# 4_ADC_Filter.net
KiCad netlist of a schematic drawn in Altium Designer
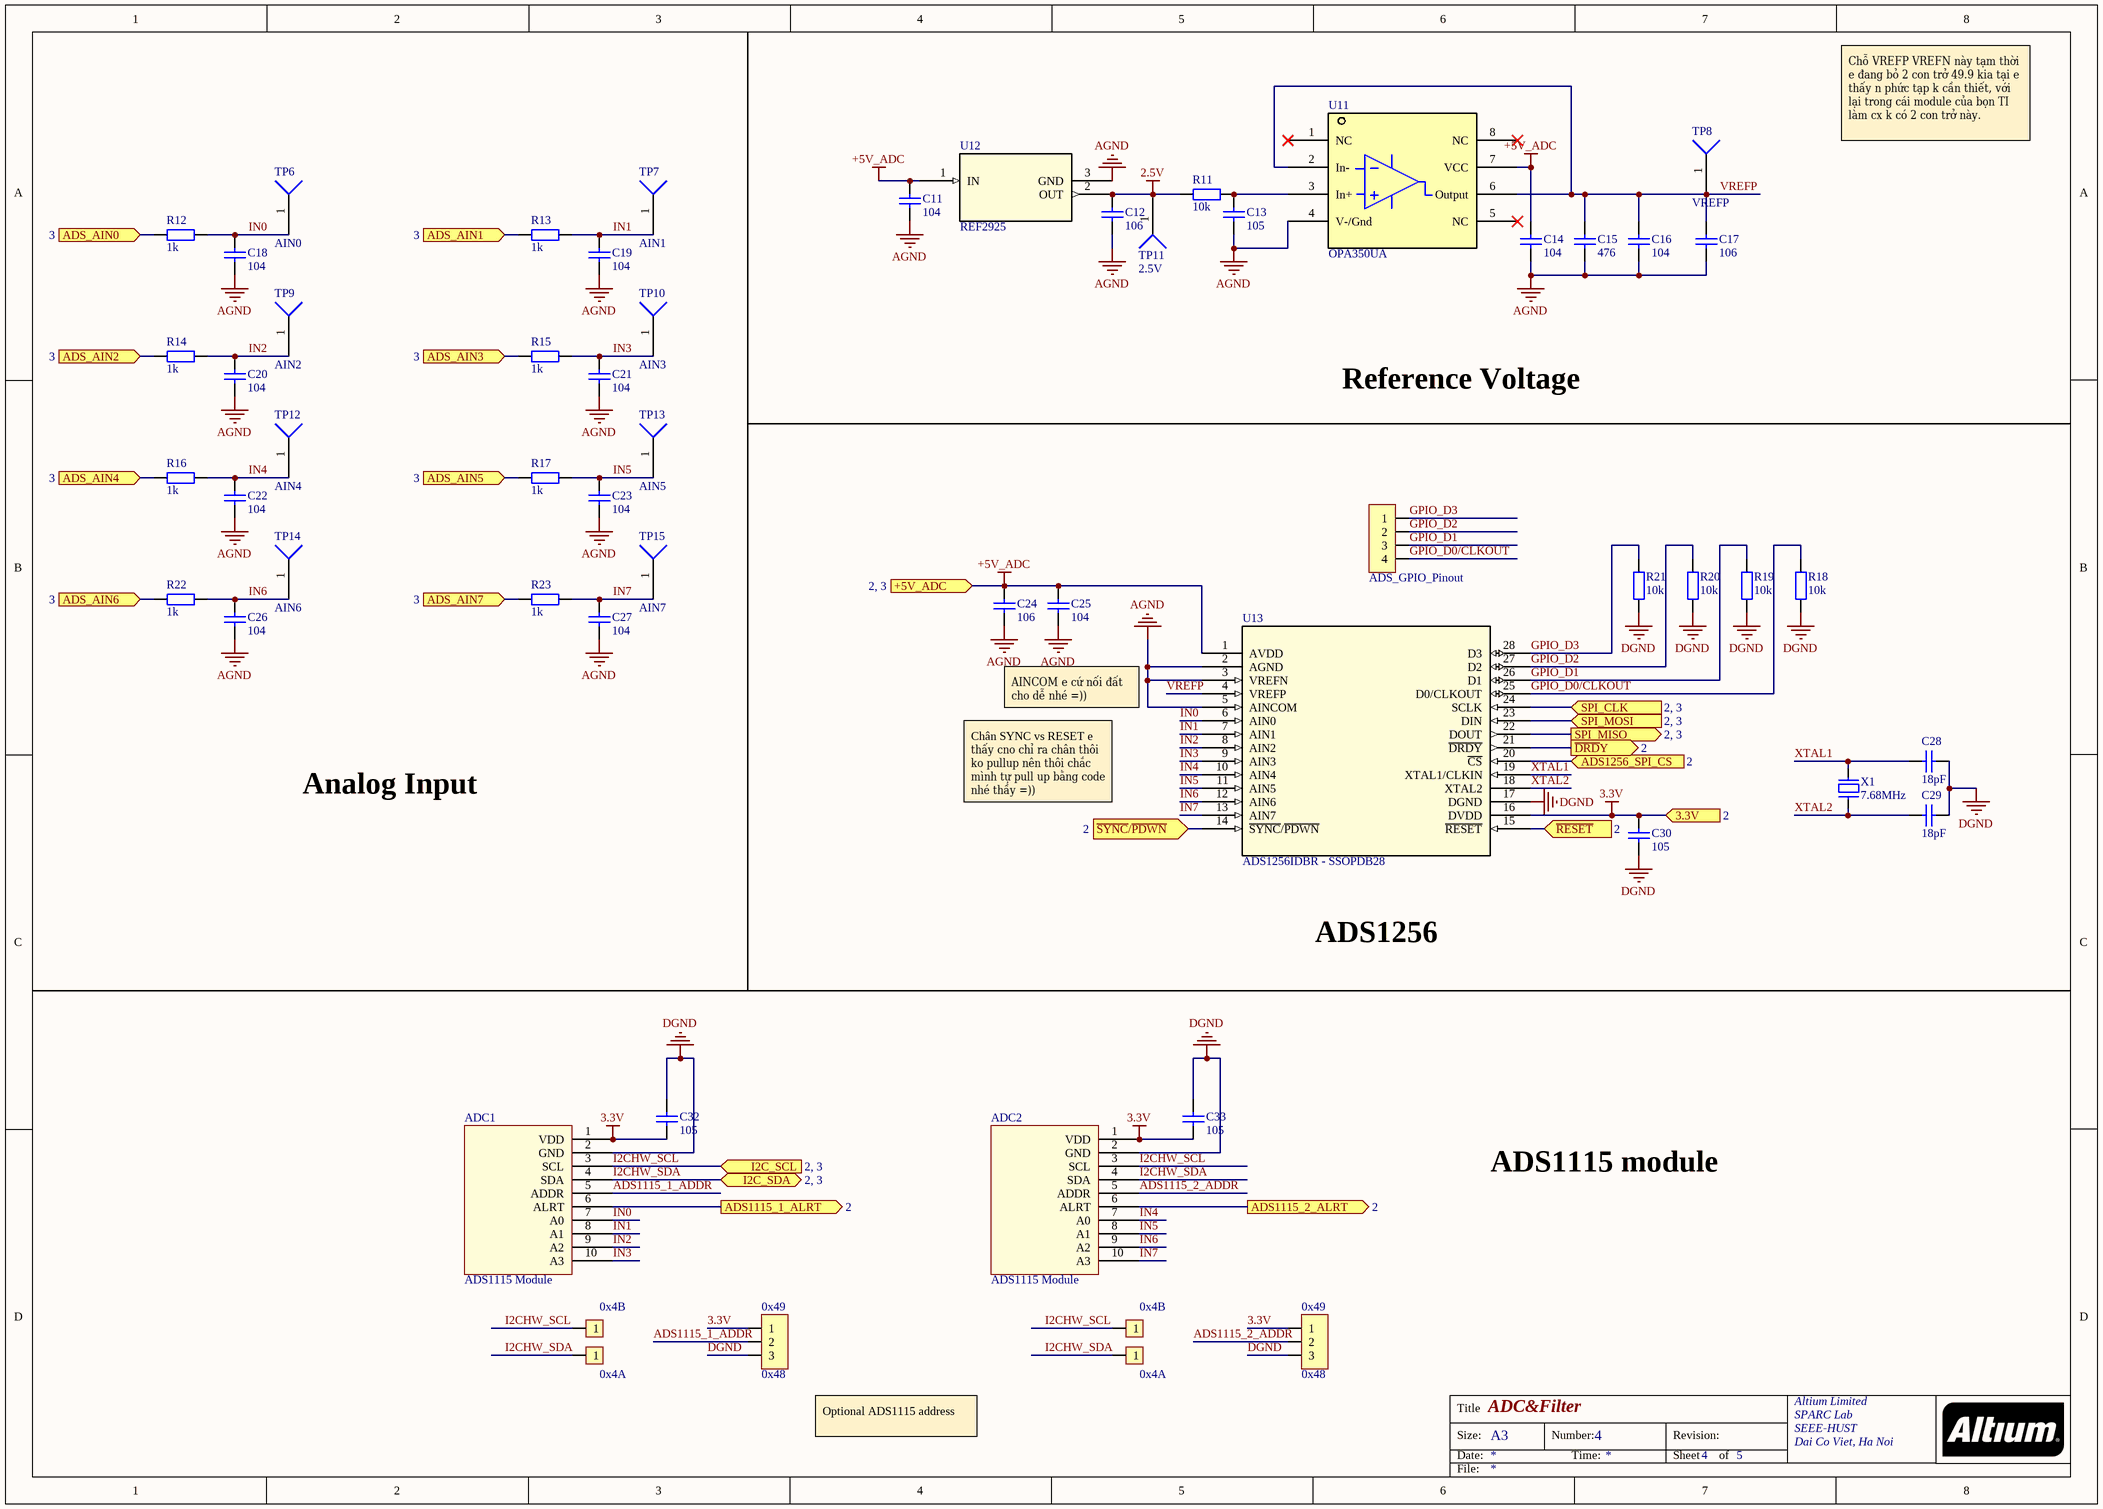
[diagram p0: [4]ADC&Filter.SchDoc]

(export (version "E")
  (design (tool "Eeschema 10.0.6"))
  (components
    (comp (ref "ADC1")
      (value "ADS1115 Module")
      (footprint "ADS1115")
      (libsource (lib "Module1") (part "ADS1115 Module ADC"))
    )
    (comp (ref "ADC2")
      (value "ADS1115 Module")
      (footprint "ADS1115")
      (libsource (lib "Module1") (part "ADS1115 Module ADC"))
    )
    (comp (ref "C11")
      (value "104")
      (footprint "tu 0805")
      (description "Dán")
      (libsource (lib "Tu dien") (part "Tu 0805 104 50V 10%"))
    )
    (comp (ref "C12")
      (value "106")
      (footprint "tu 0805")
      (description "Dán")
      (libsource (lib "Tu dien") (part "Tu 0805 106 16V 10%"))
    )
    (comp (ref "C13")
      (value "105")
      (footprint "tu 0805")
      (description "Dán")
      (libsource (lib "Tu dien") (part "Tu 0805 105 50V 10%"))
    )
    (comp (ref "C14")
      (value "104")
      (footprint "tu 0805")
      (description "Dán")
      (libsource (lib "Tu dien") (part "Tu 0805 104 50V 10%"))
    )
    (comp (ref "C15")
      (value "476")
      (footprint "tu 0805")
      (description "Dán")
      (libsource (lib "Tu dien") (part "Tu 0805 475 25V 20%"))
    )
    (comp (ref "C16")
      (value "104")
      (footprint "tu 0805")
      (description "Dán")
      (libsource (lib "Tu dien") (part "Tu 0805 104 50V 10%"))
    )
    (comp (ref "C17")
      (value "106")
      (footprint "tu 0805")
      (description "Dán")
      (libsource (lib "Tu dien") (part "Tu 0805 106 16V 10%"))
    )
    (comp (ref "C18")
      (value "104")
      (footprint "tu 0805")
      (description "Dán")
      (libsource (lib "Tu dien") (part "Tu 0805 104 50V 10%"))
    )
    (comp (ref "C19")
      (value "104")
      (footprint "tu 0805")
      (description "Dán")
      (libsource (lib "Tu dien") (part "Tu 0805 104 50V 10%"))
    )
    (comp (ref "C20")
      (value "104")
      (footprint "tu 0805")
      (description "Dán")
      (libsource (lib "Tu dien") (part "Tu 0805 104 50V 10%"))
    )
    (comp (ref "C21")
      (value "104")
      (footprint "tu 0805")
      (description "Dán")
      (libsource (lib "Tu dien") (part "Tu 0805 104 50V 10%"))
    )
    (comp (ref "C22")
      (value "104")
      (footprint "tu 0805")
      (description "Dán")
      (libsource (lib "Tu dien") (part "Tu 0805 104 50V 10%"))
    )
    (comp (ref "C23")
      (value "104")
      (footprint "tu 0805")
      (description "Dán")
      (libsource (lib "Tu dien") (part "Tu 0805 104 50V 10%"))
    )
    (comp (ref "C24")
      (value "106")
      (footprint "tu 0805")
      (description "Dán")
      (libsource (lib "Tu dien") (part "Tu 0805 106 16V 10%"))
    )
    (comp (ref "C25")
      (value "104")
      (footprint "tu 0805")
      (description "Dán")
      (libsource (lib "Tu dien") (part "Tu 0805 104 50V 10%"))
    )
    (comp (ref "C26")
      (value "104")
      (footprint "tu 0805")
      (description "Dán")
      (libsource (lib "Tu dien") (part "Tu 0805 104 50V 10%"))
    )
    (comp (ref "C27")
      (value "104")
      (footprint "tu 0805")
      (description "Dán")
      (libsource (lib "Tu dien") (part "Tu 0805 104 50V 10%"))
    )
    (comp (ref "C28")
      (value "18pF")
      (footprint "tu 0805")
      (description "Dán")
      (libsource (lib "Tu dien") (part "Tu 0805 18pF 50V 10%_1"))
    )
    (comp (ref "C29")
      (value "18pF")
      (footprint "tu 0805")
      (description "Dán")
      (libsource (lib "Tu dien") (part "Tu 0805 18pF 50V 10%_1"))
    )
    (comp (ref "C30")
      (value "105")
      (footprint "tu 0805")
      (description "Dán")
      (libsource (lib "Tu dien") (part "Tu 0805 105 50V 10%"))
    )
    (comp (ref "C32")
      (value "105")
      (footprint "tu 0805")
      (description "Dán")
      (libsource (lib "Tu dien") (part "Tu 0805 105 50V 10%"))
    )
    (comp (ref "C33")
      (value "105")
      (footprint "tu 0805")
      (description "Dán")
      (libsource (lib "Tu dien") (part "Tu 0805 105 50V 10%"))
    )
    (comp (ref "JP1")
      (value "ADS_GPIO_Pinout")
      (footprint "JP 1x4 DT")
      (description "Cắm")
      (libsource (lib "Jump") (part "JP 1x4 2.54 Duc Thang"))
    )
    (comp (ref "JP5")
      (value "JP 1x3 2.54")
      (footprint "JP 1x3 DT")
      (description "Cắm")
      (libsource (lib "Jump") (part "JP 1x3 2.54 Duc Thang"))
    )
    (comp (ref "JP6")
      (value "JP 1x3 2.54")
      (footprint "JP 1x3 DT")
      (description "Cắm")
      (libsource (lib "Jump") (part "JP 1x3 2.54 Duc Thang"))
    )
    (comp (ref "JP7")
      (value "JP 1x1 2.54")
      (footprint "JP 1x1 DT")
      (description "Cắm")
      (libsource (lib "Jump") (part "JP 1x1 2.54 Duc Thang"))
    )
    (comp (ref "JP8")
      (value "JP 1x1 2.54")
      (footprint "JP 1x1 DT")
      (description "Cắm")
      (libsource (lib "Jump") (part "JP 1x1 2.54 Duc Thang"))
    )
    (comp (ref "JP9")
      (value "JP 1x1 2.54")
      (footprint "JP 1x1 DT")
      (description "Cắm")
      (libsource (lib "Jump") (part "JP 1x1 2.54 Duc Thang"))
    )
    (comp (ref "JP10")
      (value "JP 1x1 2.54")
      (footprint "JP 1x1 DT")
      (description "Cắm")
      (libsource (lib "Jump") (part "JP 1x1 2.54 Duc Thang"))
    )
    (comp (ref "R11")
      (value "10k")
      (footprint "tro smd 0805")
      (description "Dán")
      (libsource (lib "Dien Tro") (part "Tro 0805 1% 10k"))
    )
    (comp (ref "R12")
      (value "1k")
      (footprint "tro smd 0805")
      (description "Dán")
      (libsource (lib "Dien Tro") (part "Tro 0805 1% 1k"))
    )
    (comp (ref "R13")
      (value "1k")
      (footprint "tro smd 0805")
      (description "Dán")
      (libsource (lib "Dien Tro") (part "Tro 0805 1% 1k"))
    )
    (comp (ref "R14")
      (value "1k")
      (footprint "tro smd 0805")
      (description "Dán")
      (libsource (lib "Dien Tro") (part "Tro 0805 1% 1k"))
    )
    (comp (ref "R15")
      (value "1k")
      (footprint "tro smd 0805")
      (description "Dán")
      (libsource (lib "Dien Tro") (part "Tro 0805 1% 1k"))
    )
    (comp (ref "R16")
      (value "1k")
      (footprint "tro smd 0805")
      (description "Dán")
      (libsource (lib "Dien Tro") (part "Tro 0805 1% 1k"))
    )
    (comp (ref "R17")
      (value "1k")
      (footprint "tro smd 0805")
      (description "Dán")
      (libsource (lib "Dien Tro") (part "Tro 0805 1% 1k"))
    )
    (comp (ref "R18")
      (value "10k")
      (footprint "tro smd 0805")
      (description "Dán")
      (libsource (lib "Dien Tro") (part "Tro 0805 1% 10k"))
    )
    (comp (ref "R19")
      (value "10k")
      (footprint "tro smd 0805")
      (description "Dán")
      (libsource (lib "Dien Tro") (part "Tro 0805 1% 10k"))
    )
    (comp (ref "R20")
      (value "10k")
      (footprint "tro smd 0805")
      (description "Dán")
      (libsource (lib "Dien Tro") (part "Tro 0805 1% 10k"))
    )
    (comp (ref "R21")
      (value "10k")
      (footprint "tro smd 0805")
      (description "Dán")
      (libsource (lib "Dien Tro") (part "Tro 0805 1% 10k"))
    )
    (comp (ref "R22")
      (value "1k")
      (footprint "tro smd 0805")
      (description "Dán")
      (libsource (lib "Dien Tro") (part "Tro 0805 1% 1k"))
    )
    (comp (ref "R23")
      (value "1k")
      (footprint "tro smd 0805")
      (description "Dán")
      (libsource (lib "Dien Tro") (part "Tro 0805 1% 1k"))
    )
    (comp (ref "TP6")
      (value "AIN0")
      (footprint "MinhTien_PCBLib:pad_1.65x1.65_hole_1mm")
      (description "Test Point")
      (fields (field (name "PUBLISHER") "Altium Limited"))
      (libsource (lib "MinhTien_SCHLib") (part "Test Point"))
    )
    (comp (ref "TP7")
      (value "AIN1")
      (footprint "MinhTien_PCBLib:pad_1.65x1.65_hole_1mm")
      (description "Test Point")
      (fields (field (name "PUBLISHER") "Altium Limited"))
      (libsource (lib "MinhTien_SCHLib") (part "Test Point"))
    )
    (comp (ref "TP8")
      (value "VREFP")
      (footprint "MinhTien_PCBLib:pad_1.65x1.65_hole_1mm")
      (description "Test Point")
      (fields (field (name "PUBLISHER") "Altium Limited"))
      (libsource (lib "MinhTien_SCHLib") (part "Test Point"))
    )
    (comp (ref "TP9")
      (value "AIN2")
      (footprint "MinhTien_PCBLib:pad_1.65x1.65_hole_1mm")
      (description "Test Point")
      (fields (field (name "PUBLISHER") "Altium Limited"))
      (libsource (lib "MinhTien_SCHLib") (part "Test Point"))
    )
    (comp (ref "TP10")
      (value "AIN3")
      (footprint "MinhTien_PCBLib:pad_1.65x1.65_hole_1mm")
      (description "Test Point")
      (fields (field (name "PUBLISHER") "Altium Limited"))
      (libsource (lib "MinhTien_SCHLib") (part "Test Point"))
    )
    (comp (ref "TP11")
      (value "2.5V")
      (footprint "MinhTien_PCBLib:pad_1.65x1.65_hole_1mm")
      (description "Test Point")
      (fields (field (name "PUBLISHER") "Altium Limited"))
      (libsource (lib "MinhTien_SCHLib") (part "Test Point"))
    )
    (comp (ref "TP12")
      (value "AIN4")
      (footprint "MinhTien_PCBLib:pad_1.65x1.65_hole_1mm")
      (description "Test Point")
      (fields (field (name "PUBLISHER") "Altium Limited"))
      (libsource (lib "MinhTien_SCHLib") (part "Test Point"))
    )
    (comp (ref "TP13")
      (value "AIN5")
      (footprint "MinhTien_PCBLib:pad_1.65x1.65_hole_1mm")
      (description "Test Point")
      (fields (field (name "PUBLISHER") "Altium Limited"))
      (libsource (lib "MinhTien_SCHLib") (part "Test Point"))
    )
    (comp (ref "TP14")
      (value "AIN6")
      (footprint "MinhTien_PCBLib:pad_1.65x1.65_hole_1mm")
      (description "Test Point")
      (fields (field (name "PUBLISHER") "Altium Limited"))
      (libsource (lib "MinhTien_SCHLib") (part "Test Point"))
    )
    (comp (ref "TP15")
      (value "AIN7")
      (footprint "MinhTien_PCBLib:pad_1.65x1.65_hole_1mm")
      (description "Test Point")
      (fields (field (name "PUBLISHER") "Altium Limited"))
      (libsource (lib "MinhTien_SCHLib") (part "Test Point"))
    )
    (comp (ref "U11")
      (value "OPA350UA")
      (footprint "IC:SOIC 8_127P599X175")
      (description "Op-amp OPA350")
      (libsource (lib "IC") (part "OPA350"))
    )
    (comp (ref "U12")
      (value "REF2925")
      (footprint "IC:SOT23-DBZ3")
      (description "SOT-23 CMOS 2.5V Voltage Reference")
      (libsource (lib "IC") (part "REF2925AIDBZR"))
    )
    (comp (ref "U13")
      (value "ADS1256IDBR - SSOPDB28")
      (footprint "IC:SSOPDB28")
      (description "Very Low Noise, 24-Bit Analog-to-Digital Converter")
      (libsource (lib "IC") (part "ADS1256IDBR - SSOPDB28"))
    )
    (comp (ref "X1")
      (value "7.68MHz")
      (footprint "Thach Anh 2 chan SMD")
      (description "Crystal For all Crystal 2pin.")
      (libsource (lib "Component") (part "Thach Anh 2 chan SMD"))
    )
  )
  (nets
    (net (code "1") (name "+5V_ADC") (class "Default")
      (node (ref "C11") (pin "1") (pinfunction "1_1") (pintype "passive"))
      (node (ref "C14") (pin "1") (pinfunction "1_1") (pintype "passive"))
      (node (ref "C24") (pin "1") (pinfunction "1_1") (pintype "passive"))
      (node (ref "C25") (pin "1") (pinfunction "1_1") (pintype "passive"))
      (node (ref "U11") (pin "7") (pinfunction "VCC_7") (pintype "passive"))
      (node (ref "U12") (pin "1") (pinfunction "IN_1") (pintype "input"))
      (node (ref "U13") (pin "1") (pinfunction "AVDD_1") (pintype "power_in"))
    )
    (net (code "2") (name "/ADS1115_1_ADDR") (class "Default")
      (node (ref "ADC1") (pin "5") (pinfunction "ADDR_5") (pintype "passive"))
      (node (ref "JP5") (pin "2") (pinfunction "2_2") (pintype "passive"))
    )
    (net (code "3") (name "/ADS1115_1_ALRT") (class "Default")
      (node (ref "ADC1") (pin "6") (pinfunction "ALRT_6") (pintype "passive"))
    )
    (net (code "4") (name "/ADS1115_2_ADDR") (class "Default")
      (node (ref "ADC2") (pin "5") (pinfunction "ADDR_5") (pintype "passive"))
      (node (ref "JP6") (pin "2") (pinfunction "2_2") (pintype "passive"))
    )
    (net (code "5") (name "/ADS1115_2_ALRT") (class "Default")
      (node (ref "ADC2") (pin "6") (pinfunction "ALRT_6") (pintype "passive"))
    )
    (net (code "6") (name "/ADS1256_SPI_CS") (class "Default")
      (node (ref "U13") (pin "20") (pinfunction "~{CS}_20") (pintype "input"))
    )
    (net (code "7") (name "/ADS_AIN0") (class "Default")
      (node (ref "R12") (pin "1") (pinfunction "1_1") (pintype "passive"))
    )
    (net (code "8") (name "/ADS_AIN1") (class "Default")
      (node (ref "R13") (pin "1") (pinfunction "1_1") (pintype "passive"))
    )
    (net (code "9") (name "/ADS_AIN2") (class "Default")
      (node (ref "R14") (pin "1") (pinfunction "1_1") (pintype "passive"))
    )
    (net (code "10") (name "/ADS_AIN3") (class "Default")
      (node (ref "R15") (pin "1") (pinfunction "1_1") (pintype "passive"))
    )
    (net (code "11") (name "/ADS_AIN4") (class "Default")
      (node (ref "R16") (pin "1") (pinfunction "1_1") (pintype "passive"))
    )
    (net (code "12") (name "/ADS_AIN5") (class "Default")
      (node (ref "R17") (pin "1") (pinfunction "1_1") (pintype "passive"))
    )
    (net (code "13") (name "/ADS_AIN6") (class "Default")
      (node (ref "R22") (pin "1") (pinfunction "1_1") (pintype "passive"))
    )
    (net (code "14") (name "/ADS_AIN7") (class "Default")
      (node (ref "R23") (pin "1") (pinfunction "1_1") (pintype "passive"))
    )
    (net (code "15") (name "/GPIO_D0{slash}CLKOUT") (class "Default")
      (node (ref "JP1") (pin "4") (pinfunction "4_4") (pintype "passive"))
      (node (ref "R18") (pin "2") (pinfunction "2_2") (pintype "passive"))
      (node (ref "U13") (pin "25") (pinfunction "D0/CLKOUT_25") (pintype "bidirectional"))
    )
    (net (code "16") (name "/GPIO_D1") (class "Default")
      (node (ref "JP1") (pin "3") (pinfunction "3_3") (pintype "passive"))
      (node (ref "R19") (pin "1") (pinfunction "1_1") (pintype "passive"))
      (node (ref "U13") (pin "26") (pinfunction "D1_26") (pintype "bidirectional"))
    )
    (net (code "17") (name "/GPIO_D2") (class "Default")
      (node (ref "JP1") (pin "2") (pinfunction "2_2") (pintype "passive"))
      (node (ref "R20") (pin "1") (pinfunction "1_1") (pintype "passive"))
      (node (ref "U13") (pin "27") (pinfunction "D2_27") (pintype "bidirectional"))
    )
    (net (code "18") (name "/GPIO_D3") (class "Default")
      (node (ref "JP1") (pin "1") (pinfunction "1_1") (pintype "passive"))
      (node (ref "R21") (pin "1") (pinfunction "1_1") (pintype "passive"))
      (node (ref "U13") (pin "28") (pinfunction "D3_28") (pintype "bidirectional"))
    )
    (net (code "19") (name "/I2CHW_SCL") (class "Default")
      (node (ref "ADC1") (pin "3") (pinfunction "SCL_3") (pintype "passive"))
      (node (ref "ADC2") (pin "3") (pinfunction "SCL_3") (pintype "passive"))
      (node (ref "JP7") (pin "1") (pinfunction "1_1") (pintype "passive"))
      (node (ref "JP8") (pin "1") (pinfunction "1_1") (pintype "passive"))
    )
    (net (code "20") (name "/I2CHW_SDA") (class "Default")
      (node (ref "ADC1") (pin "4") (pinfunction "SDA_4") (pintype "passive"))
      (node (ref "ADC2") (pin "4") (pinfunction "SDA_4") (pintype "passive"))
      (node (ref "JP10") (pin "1") (pinfunction "1_1") (pintype "passive"))
      (node (ref "JP9") (pin "1") (pinfunction "1_1") (pintype "passive"))
    )
    (net (code "21") (name "/IN0") (class "Default")
      (node (ref "ADC1") (pin "7") (pinfunction "A0_7") (pintype "passive"))
      (node (ref "C18") (pin "1") (pinfunction "1_1") (pintype "passive"))
      (node (ref "R12") (pin "2") (pinfunction "2_2") (pintype "passive"))
      (node (ref "TP6") (pin "1") (pinfunction "1_1") (pintype "passive"))
      (node (ref "U13") (pin "6") (pinfunction "AIN0_6") (pintype "input"))
    )
    (net (code "22") (name "/IN1") (class "Default")
      (node (ref "ADC1") (pin "8") (pinfunction "A1_8") (pintype "passive"))
      (node (ref "C19") (pin "1") (pinfunction "1_1") (pintype "passive"))
      (node (ref "R13") (pin "2") (pinfunction "2_2") (pintype "passive"))
      (node (ref "TP7") (pin "1") (pinfunction "1_1") (pintype "passive"))
      (node (ref "U13") (pin "7") (pinfunction "AIN1_7") (pintype "input"))
    )
    (net (code "23") (name "/IN2") (class "Default")
      (node (ref "ADC1") (pin "9") (pinfunction "A2_9") (pintype "passive"))
      (node (ref "C20") (pin "1") (pinfunction "1_1") (pintype "passive"))
      (node (ref "R14") (pin "2") (pinfunction "2_2") (pintype "passive"))
      (node (ref "TP9") (pin "1") (pinfunction "1_1") (pintype "passive"))
      (node (ref "U13") (pin "8") (pinfunction "AIN2_8") (pintype "input"))
    )
    (net (code "24") (name "/IN3") (class "Default")
      (node (ref "ADC1") (pin "10") (pinfunction "A3_10") (pintype "passive"))
      (node (ref "C21") (pin "1") (pinfunction "1_1") (pintype "passive"))
      (node (ref "R15") (pin "2") (pinfunction "2_2") (pintype "passive"))
      (node (ref "TP10") (pin "1") (pinfunction "1_1") (pintype "passive"))
      (node (ref "U13") (pin "9") (pinfunction "AIN3_9") (pintype "input"))
    )
    (net (code "25") (name "/IN4") (class "Default")
      (node (ref "ADC2") (pin "7") (pinfunction "A0_7") (pintype "passive"))
      (node (ref "C22") (pin "1") (pinfunction "1_1") (pintype "passive"))
      (node (ref "R16") (pin "2") (pinfunction "2_2") (pintype "passive"))
      (node (ref "TP12") (pin "1") (pinfunction "1_1") (pintype "passive"))
      (node (ref "U13") (pin "10") (pinfunction "AIN4_10") (pintype "input"))
    )
    (net (code "26") (name "/IN5") (class "Default")
      (node (ref "ADC2") (pin "8") (pinfunction "A1_8") (pintype "passive"))
      (node (ref "C23") (pin "1") (pinfunction "1_1") (pintype "passive"))
      (node (ref "R17") (pin "2") (pinfunction "2_2") (pintype "passive"))
      (node (ref "TP13") (pin "1") (pinfunction "1_1") (pintype "passive"))
      (node (ref "U13") (pin "11") (pinfunction "AIN5_11") (pintype "input"))
    )
    (net (code "27") (name "/IN6") (class "Default")
      (node (ref "ADC2") (pin "9") (pinfunction "A2_9") (pintype "passive"))
      (node (ref "C26") (pin "1") (pinfunction "1_1") (pintype "passive"))
      (node (ref "R22") (pin "2") (pinfunction "2_2") (pintype "passive"))
      (node (ref "TP14") (pin "1") (pinfunction "1_1") (pintype "passive"))
      (node (ref "U13") (pin "12") (pinfunction "AIN6_12") (pintype "input"))
    )
    (net (code "28") (name "/IN7") (class "Default")
      (node (ref "ADC2") (pin "10") (pinfunction "A3_10") (pintype "passive"))
      (node (ref "C27") (pin "1") (pinfunction "1_1") (pintype "passive"))
      (node (ref "R23") (pin "2") (pinfunction "2_2") (pintype "passive"))
      (node (ref "TP15") (pin "1") (pinfunction "1_1") (pintype "passive"))
      (node (ref "U13") (pin "13") (pinfunction "AIN7_13") (pintype "input"))
    )
    (net (code "29") (name "/SPI_CLK") (class "Default")
      (node (ref "U13") (pin "24") (pinfunction "SCLK_24") (pintype "input"))
    )
    (net (code "30") (name "/SPI_MISO") (class "Default")
      (node (ref "U13") (pin "22") (pinfunction "DOUT_22") (pintype "output"))
    )
    (net (code "31") (name "/SPI_MOSI") (class "Default")
      (node (ref "U13") (pin "23") (pinfunction "DIN_23") (pintype "input"))
    )
    (net (code "32") (name "/VREFP") (class "Default")
      (node (ref "C15") (pin "1") (pinfunction "1_1") (pintype "passive"))
      (node (ref "C16") (pin "1") (pinfunction "1_1") (pintype "passive"))
      (node (ref "C17") (pin "1") (pinfunction "1_1") (pintype "passive"))
      (node (ref "TP8") (pin "1") (pinfunction "1_1") (pintype "passive"))
      (node (ref "U11") (pin "2") (pinfunction "In-_2") (pintype "passive"))
      (node (ref "U11") (pin "6") (pinfunction "Output_6") (pintype "passive"))
      (node (ref "U13") (pin "4") (pinfunction "VREFP_4") (pintype "input"))
    )
    (net (code "33") (name "/XTAL1") (class "Default")
      (node (ref "C28") (pin "2") (pinfunction "2_2") (pintype "passive"))
      (node (ref "U13") (pin "19") (pinfunction "XTAL1/CLKIN_19") (pintype "input"))
      (node (ref "X1") (pin "2") (pinfunction "2_2") (pintype "passive"))
    )
    (net (code "34") (name "/XTAL2") (class "Default")
      (node (ref "C29") (pin "2") (pinfunction "2_2") (pintype "passive"))
      (node (ref "U13") (pin "18") (pinfunction "XTAL2_18") (pintype "passive"))
      (node (ref "X1") (pin "1") (pinfunction "1_1") (pintype "passive"))
    )
    (net (code "35") (name "/~{DRD}Y") (class "Default")
      (node (ref "U13") (pin "21") (pinfunction "~{DRDY}_21") (pintype "output"))
    )
    (net (code "36") (name "/~{RESET}") (class "Default")
      (node (ref "U13") (pin "15") (pinfunction "~{RESET}_15") (pintype "input"))
    )
    (net (code "37") (name "/~{SYNC}{slash}~{PDWN}") (class "Default")
      (node (ref "U13") (pin "14") (pinfunction "~{SYNC}/~{PDWN}_14") (pintype "input"))
    )
    (net (code "38") (name "2.5V") (class "Default")
      (node (ref "C12") (pin "1") (pinfunction "1_1") (pintype "passive"))
      (node (ref "R11") (pin "1") (pinfunction "1_1") (pintype "passive"))
      (node (ref "TP11") (pin "1") (pinfunction "1_1") (pintype "passive"))
      (node (ref "U12") (pin "2") (pinfunction "OUT_2") (pintype "output"))
    )
    (net (code "39") (name "3.3V") (class "Default")
      (node (ref "ADC1") (pin "1") (pinfunction "VDD_1") (pintype "passive"))
      (node (ref "ADC2") (pin "1") (pinfunction "VDD_1") (pintype "passive"))
      (node (ref "C30") (pin "1") (pinfunction "1_1") (pintype "passive"))
      (node (ref "C32") (pin "1") (pinfunction "1_1") (pintype "passive"))
      (node (ref "C33") (pin "1") (pinfunction "1_1") (pintype "passive"))
      (node (ref "JP5") (pin "1") (pinfunction "1_1") (pintype "passive"))
      (node (ref "JP6") (pin "1") (pinfunction "1_1") (pintype "passive"))
      (node (ref "U13") (pin "16") (pinfunction "DVDD_16") (pintype "power_in"))
    )
    (net (code "40") (name "AGND") (class "Default")
      (node (ref "C11") (pin "2") (pinfunction "2_2") (pintype "passive"))
      (node (ref "C12") (pin "2") (pinfunction "2_2") (pintype "passive"))
      (node (ref "C13") (pin "2") (pinfunction "2_2") (pintype "passive"))
      (node (ref "C14") (pin "2") (pinfunction "2_2") (pintype "passive"))
      (node (ref "C15") (pin "2") (pinfunction "2_2") (pintype "passive"))
      (node (ref "C16") (pin "2") (pinfunction "2_2") (pintype "passive"))
      (node (ref "C17") (pin "2") (pinfunction "2_2") (pintype "passive"))
      (node (ref "C18") (pin "2") (pinfunction "2_2") (pintype "passive"))
      (node (ref "C19") (pin "2") (pinfunction "2_2") (pintype "passive"))
      (node (ref "C20") (pin "2") (pinfunction "2_2") (pintype "passive"))
      (node (ref "C21") (pin "2") (pinfunction "2_2") (pintype "passive"))
      (node (ref "C22") (pin "2") (pinfunction "2_2") (pintype "passive"))
      (node (ref "C23") (pin "2") (pinfunction "2_2") (pintype "passive"))
      (node (ref "C24") (pin "2") (pinfunction "2_2") (pintype "passive"))
      (node (ref "C25") (pin "2") (pinfunction "2_2") (pintype "passive"))
      (node (ref "C26") (pin "2") (pinfunction "2_2") (pintype "passive"))
      (node (ref "C27") (pin "2") (pinfunction "2_2") (pintype "passive"))
      (node (ref "U11") (pin "4") (pinfunction "V-/Gnd_4") (pintype "passive"))
      (node (ref "U12") (pin "3") (pinfunction "GND_3") (pintype "power_in"))
      (node (ref "U13") (pin "2") (pinfunction "AGND_2") (pintype "power_in"))
      (node (ref "U13") (pin "3") (pinfunction "VREFN_3") (pintype "input"))
      (node (ref "U13") (pin "5") (pinfunction "AINCOM_5") (pintype "input"))
    )
    (net (code "41") (name "DGND") (class "Default")
      (node (ref "ADC1") (pin "2") (pinfunction "GND_2") (pintype "passive"))
      (node (ref "ADC2") (pin "2") (pinfunction "GND_2") (pintype "passive"))
      (node (ref "C28") (pin "1") (pinfunction "1_1") (pintype "passive"))
      (node (ref "C29") (pin "1") (pinfunction "1_1") (pintype "passive"))
      (node (ref "C30") (pin "2") (pinfunction "2_2") (pintype "passive"))
      (node (ref "C32") (pin "2") (pinfunction "2_2") (pintype "passive"))
      (node (ref "C33") (pin "2") (pinfunction "2_2") (pintype "passive"))
      (node (ref "JP5") (pin "3") (pinfunction "3_3") (pintype "passive"))
      (node (ref "JP6") (pin "3") (pinfunction "3_3") (pintype "passive"))
      (node (ref "R18") (pin "1") (pinfunction "1_1") (pintype "passive"))
      (node (ref "R19") (pin "2") (pinfunction "2_2") (pintype "passive"))
      (node (ref "R20") (pin "2") (pinfunction "2_2") (pintype "passive"))
      (node (ref "R21") (pin "2") (pinfunction "2_2") (pintype "passive"))
      (node (ref "U13") (pin "17") (pinfunction "DGND_17") (pintype "power_in"))
    )
    (net (code "42") (name "Net-(U11-In+)") (class "Default")
      (node (ref "C13") (pin "1") (pinfunction "1_1") (pintype "passive"))
      (node (ref "R11") (pin "2") (pinfunction "2_2") (pintype "passive"))
      (node (ref "U11") (pin "3") (pinfunction "In+_3") (pintype "passive"))
    )
    (net (code "43") (name "unconnected-(U11-NC-Pad1)") (class "Default")
      (node (ref "U11") (pin "1") (pinfunction "NC_1") (pintype "passive+no_connect"))
    )
    (net (code "44") (name "unconnected-(U11-NC-Pad5)") (class "Default")
      (node (ref "U11") (pin "5") (pinfunction "NC_5") (pintype "passive+no_connect"))
    )
    (net (code "45") (name "unconnected-(U11-NC-Pad8)") (class "Default")
      (node (ref "U11") (pin "8") (pinfunction "NC_8") (pintype "passive+no_connect"))
    )
  )
)
